# Sheet1.net
KiCad netlist of a schematic drawn in Altium Designer
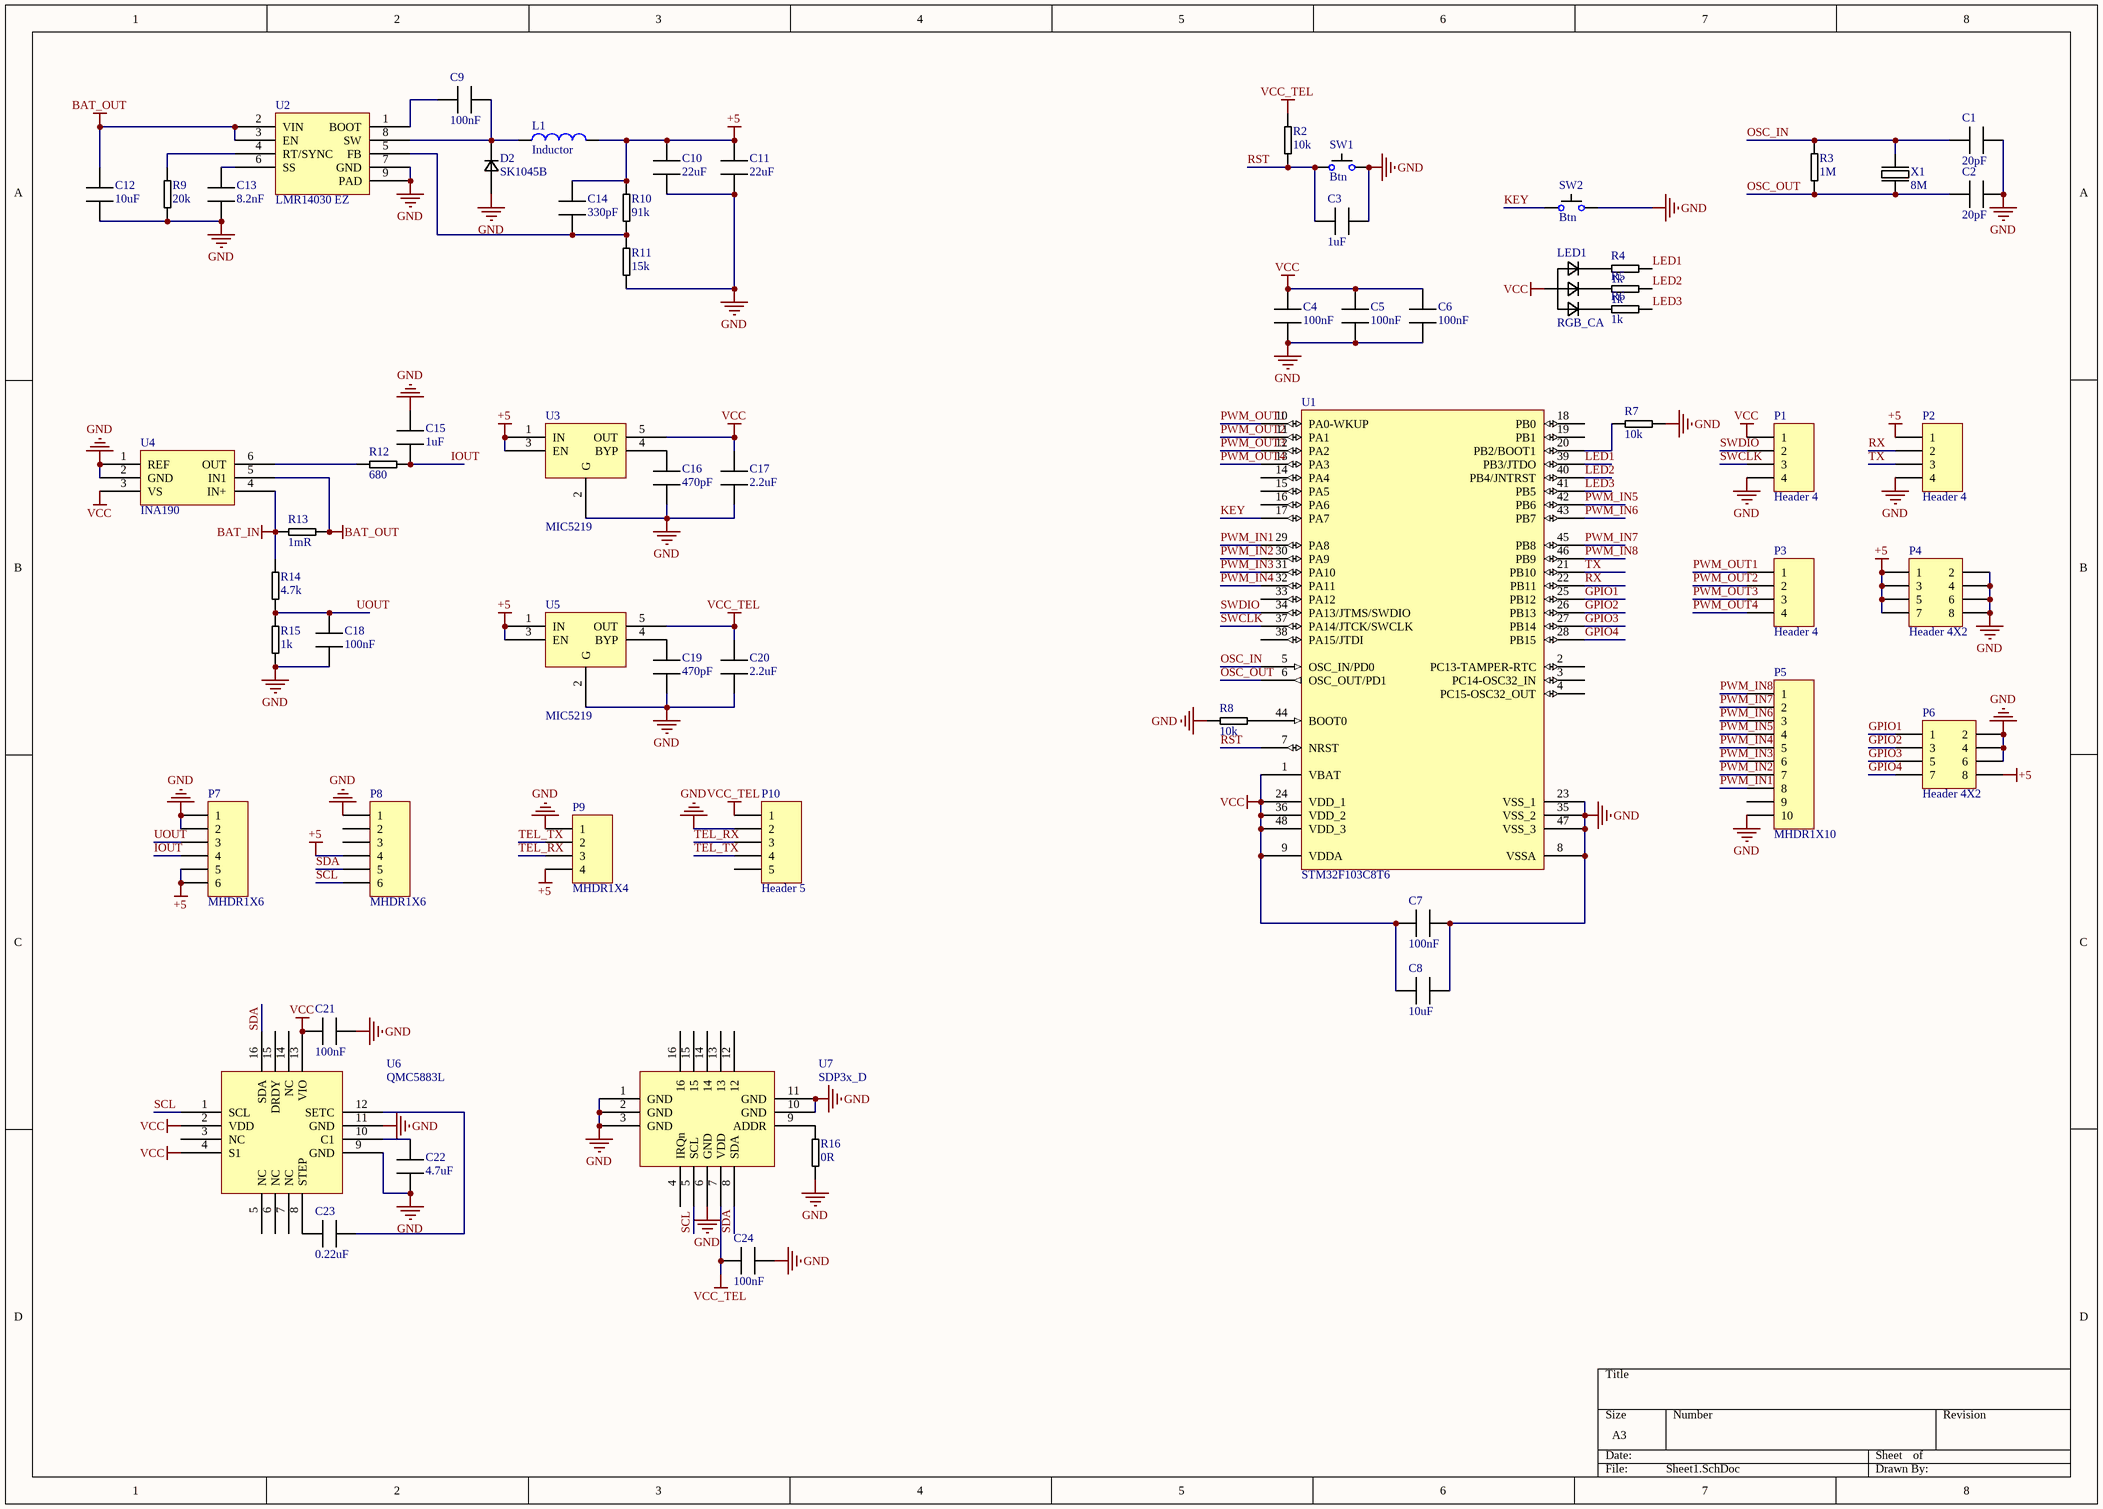
[diagram p0: Sheet1.SchDoc]

(export (version "E")
  (design (tool "Eeschema 10.0.6"))
  (components
    (comp (ref "C1") (value "20pF") (footprint "0603") (libsource (lib "LibCfrpg") (part "Cap")))
    (comp (ref "C2") (value "20pF") (footprint "0603") (libsource (lib "LibCfrpg") (part "Cap")))
    (comp (ref "C3") (value "1uF") (footprint "0603") (libsource (lib "LibCfrpg") (part "Cap")))
    (comp (ref "C4") (value "100nF") (footprint "0603") (libsource (lib "LibCfrpg") (part "Cap")))
    (comp (ref "C5") (value "100nF") (footprint "0603") (libsource (lib "LibCfrpg") (part "Cap")))
    (comp (ref "C6") (value "100nF") (footprint "0603") (libsource (lib "LibCfrpg") (part "Cap")))
    (comp (ref "C7") (value "100nF") (footprint "0603") (libsource (lib "LibCfrpg") (part "Cap")))
    (comp (ref "C8") (value "10uF") (footprint "0603") (libsource (lib "LibCfrpg") (part "Cap")))
    (comp (ref "C9") (value "100nF") (footprint "0603") (libsource (lib "LibCfrpg") (part "Cap")))
    (comp (ref "C10") (value "22uF") (footprint "0603") (libsource (lib "LibCfrpg") (part "Cap")))
    (comp (ref "C11") (value "22uF") (footprint "0603") (libsource (lib "LibCfrpg") (part "Cap")))
    (comp (ref "C12") (value "10uF") (footprint "1210") (libsource (lib "LibCfrpg") (part "Cap")))
    (comp (ref "C13") (value "8.2nF") (footprint "0603") (libsource (lib "LibCfrpg") (part "Cap")))
    (comp (ref "C14") (value "330pF") (footprint "0603") (libsource (lib "LibCfrpg") (part "Cap")))
    (comp (ref "C15") (value "1uF") (footprint "0603") (libsource (lib "LibCfrpg") (part "Cap")))
    (comp (ref "C16") (value "470pF") (footprint "0603") (libsource (lib "LibCfrpg") (part "Cap")))
    (comp (ref "C17") (value "2.2uF") (footprint "0603") (libsource (lib "LibCfrpg") (part "Cap")))
    (comp (ref "C18") (value "100nF") (footprint "0603") (libsource (lib "LibCfrpg") (part "Cap")))
    (comp (ref "C19") (value "470pF") (footprint "0603") (libsource (lib "LibCfrpg") (part "Cap")))
    (comp (ref "C20") (value "2.2uF") (footprint "0603") (libsource (lib "LibCfrpg") (part "Cap")))
    (comp (ref "C21") (value "100nF") (footprint "0603") (libsource (lib "LibCfrpg") (part "Cap")))
    (comp (ref "C22") (value "4.7uF") (footprint "0603") (libsource (lib "LibCfrpg") (part "Cap")))
    (comp (ref "C23") (value "0.22uF") (footprint "0603") (libsource (lib "LibCfrpg") (part "Cap")))
    (comp (ref "C24") (value "100nF") (footprint "0603") (libsource (lib "LibCfrpg") (part "Cap")))
    (comp (ref "D2")
      (value "SK1045B")
      (footprint "SMB (DO-214AA)")
      (libsource (lib "LibCfrpg") (part "Diode"))
    )
    (comp (ref "L1") (value "Inductor") (footprint "Ind1040") (libsource (lib "LibCfrpg") (part "Inductor")))
    (comp (ref "LED1") (value "RGB_CA") (footprint "RGB1.6*1.6") (libsource (lib "LibCfrpg") (part "RGB_CA")))
    (comp (ref "P1")
      (value "Header 4")
      (footprint "HDR1X4")
      (description "Header, 4-Pin")
      (fields (field (name "PUBLISHER") "Altium Limited"))
      (libsource (lib "Miscellaneous Connectors") (part "Header 4"))
    )
    (comp (ref "P2")
      (value "Header 4")
      (footprint "HDR1X4")
      (description "Header, 4-Pin")
      (fields (field (name "PUBLISHER") "Altium Limited"))
      (libsource (lib "Miscellaneous Connectors") (part "Header 4"))
    )
    (comp (ref "P3")
      (value "Header 4")
      (footprint "HDR1X4")
      (description "Header, 4-Pin")
      (fields (field (name "PUBLISHER") "Altium Limited"))
      (libsource (lib "Miscellaneous Connectors") (part "Header 4"))
    )
    (comp (ref "P4")
      (value "Header 4X2")
      (footprint "HDR2X4")
      (description "Header, 4-Pin, Dual row")
      (fields (field (name "PUBLISHER") "Altium Limited"))
      (libsource (lib "Miscellaneous Connectors") (part "Header 4X2"))
    )
    (comp (ref "P5")
      (value "MHDR1X10")
      (footprint "MHDR1X10")
      (description "Header, 10-Pin")
      (fields (field (name "PUBLISHER") "Altium Limited"))
      (libsource (lib "Miscellaneous Connectors") (part "MHDR1X10"))
    )
    (comp (ref "P6")
      (value "Header 4X2")
      (footprint "HDR2X4")
      (description "Header, 4-Pin, Dual row")
      (fields (field (name "PUBLISHER") "Altium Limited"))
      (libsource (lib "Miscellaneous Connectors") (part "Header 4X2"))
    )
    (comp (ref "P7")
      (value "MHDR1X6")
      (footprint "MHDR1X6")
      (description "Header, 6-Pin")
      (fields (field (name "PUBLISHER") "Altium Limited"))
      (libsource (lib "Miscellaneous Connectors") (part "MHDR1X6"))
    )
    (comp (ref "P8")
      (value "MHDR1X6")
      (footprint "MHDR1X6")
      (description "Header, 6-Pin")
      (fields (field (name "PUBLISHER") "Altium Limited"))
      (libsource (lib "Miscellaneous Connectors") (part "MHDR1X6"))
    )
    (comp (ref "P9")
      (value "MHDR1X4")
      (footprint "MHDR1X4")
      (description "Header, 4-Pin")
      (fields (field (name "PUBLISHER") "Altium Limited"))
      (libsource (lib "Miscellaneous Connectors") (part "MHDR1X4"))
    )
    (comp (ref "P10")
      (value "Header 5")
      (footprint "HDR1X5")
      (description "Header, 5-Pin")
      (fields (field (name "PUBLISHER") "Altium Limited"))
      (libsource (lib "Miscellaneous Connectors") (part "Header 5"))
    )
    (comp (ref "R2") (value "10k") (footprint "0603") (libsource (lib "LibCfrpg") (part "Res")))
    (comp (ref "R3") (value "1M") (footprint "0603") (libsource (lib "LibCfrpg") (part "Res")))
    (comp (ref "R4") (value "1k") (footprint "0603") (libsource (lib "LibCfrpg") (part "Res")))
    (comp (ref "R5") (value "1k") (footprint "0603") (libsource (lib "LibCfrpg") (part "Res")))
    (comp (ref "R6") (value "1k") (footprint "0603") (libsource (lib "LibCfrpg") (part "Res")))
    (comp (ref "R7") (value "10k") (footprint "0603") (libsource (lib "LibCfrpg") (part "Res")))
    (comp (ref "R8") (value "10k") (footprint "0603") (libsource (lib "LibCfrpg") (part "Res")))
    (comp (ref "R9") (value "20k") (footprint "0603") (libsource (lib "LibCfrpg") (part "Res")))
    (comp (ref "R10") (value "91k") (footprint "0603") (libsource (lib "LibCfrpg") (part "Res")))
    (comp (ref "R11") (value "15k") (footprint "0603") (libsource (lib "LibCfrpg") (part "Res")))
    (comp (ref "R12") (value "680") (footprint "0603") (libsource (lib "LibCfrpg") (part "Res")))
    (comp (ref "R13") (value "1mR") (footprint "2512") (libsource (lib "LibCfrpg") (part "Res")))
    (comp (ref "R14") (value "4.7k") (footprint "0603") (libsource (lib "LibCfrpg") (part "Res")))
    (comp (ref "R15") (value "1k") (footprint "0603") (libsource (lib "LibCfrpg") (part "Res")))
    (comp (ref "R16") (value "0R") (footprint "0603") (libsource (lib "LibCfrpg") (part "Res")))
    (comp (ref "SW1") (value "Btn") (footprint "BTN_B3U_B") (libsource (lib "LibCfrpg") (part "Btn")))
    (comp (ref "SW2") (value "Btn") (footprint "BTN_B3U_B") (libsource (lib "LibCfrpg") (part "Btn")))
    (comp (ref "U1")
      (value "STM32F103C8T6")
      (footprint "LQFP48_N")
      (description "STM32 ARM-based 32-bit MCU with 64 Kbytes Flash, 48-pin LQFP, Industrial Temperature")
      (fields (field (name "PUBLISHER") "Altium Limited"))
      (libsource (lib "ST Microcontroller 32-Bit STM32") (part "STM32F103C8T6"))
    )
    (comp (ref "U2")
      (value "LMR14030 EZ")
      (footprint "SOP8-Pad")
      (libsource (lib "LibCfrpg") (part "LMR14030 EZ"))
    )
    (comp (ref "U3") (value "MIC5219") (footprint "SOT23-5") (libsource (lib "LibCfrpg") (part "MIC5219")))
    (comp (ref "U4") (value "INA190") (footprint "SC70") (libsource (lib "LibCfrpg") (part "INA190")))
    (comp (ref "U5") (value "MIC5219") (footprint "SOT23-5") (libsource (lib "LibCfrpg") (part "MIC5219")))
    (comp (ref "U6") (value "QMC5883L") (footprint "QMC5883") (libsource (lib "LibCfrpg") (part "QMC5883L")))
    (comp (ref "U7") (value "SDP3x_D") (footprint "SDP3x") (libsource (lib "LibCfrpg") (part "SDP3x_D")))
    (comp (ref "X1") (value "8M") (footprint "XTAL-3225-4") (libsource (lib "LibCfrpg") (part "XTAL")))
  )
  (nets
    (net (code "1") (name "+5") (class "Default")
      (node (ref "C10") (pin "2") (pintype "passive"))
      (node (ref "C11") (pin "2") (pintype "passive"))
      (node (ref "C14") (pin "2") (pintype "passive"))
      (node (ref "L1") (pin "2") (pinfunction "2_2") (pintype "passive"))
      (node (ref "P2") (pin "1") (pinfunction "1_1") (pintype "passive"))
      (node (ref "P4") (pin "1") (pinfunction "1_1") (pintype "passive"))
      (node (ref "P4") (pin "3") (pinfunction "3_3") (pintype "passive"))
      (node (ref "P4") (pin "5") (pinfunction "5_5") (pintype "passive"))
      (node (ref "P4") (pin "7") (pinfunction "7_7") (pintype "passive"))
      (node (ref "P6") (pin "8") (pinfunction "8_8") (pintype "passive"))
      (node (ref "P7") (pin "5") (pinfunction "5_5") (pintype "passive"))
      (node (ref "P7") (pin "6") (pinfunction "6_6") (pintype "passive"))
      (node (ref "P8") (pin "4") (pinfunction "4_4") (pintype "passive"))
      (node (ref "P9") (pin "4") (pinfunction "4_4") (pintype "passive"))
      (node (ref "R10") (pin "2") (pintype "passive"))
      (node (ref "U3") (pin "1") (pinfunction "IN_1") (pintype "passive"))
      (node (ref "U3") (pin "3") (pinfunction "EN_3") (pintype "passive"))
      (node (ref "U5") (pin "1") (pinfunction "IN_1") (pintype "passive"))
      (node (ref "U5") (pin "3") (pinfunction "EN_3") (pintype "passive"))
    )
    (net (code "2") (name "/GPIO1") (class "Default")
      (node (ref "P6") (pin "1") (pinfunction "1_1") (pintype "passive"))
      (node (ref "U1") (pin "25") (pinfunction "PB12_25") (pintype "bidirectional"))
    )
    (net (code "3") (name "/GPIO2") (class "Default")
      (node (ref "P6") (pin "3") (pinfunction "3_3") (pintype "passive"))
      (node (ref "U1") (pin "26") (pinfunction "PB13_26") (pintype "bidirectional"))
    )
    (net (code "4") (name "/GPIO3") (class "Default")
      (node (ref "P6") (pin "5") (pinfunction "5_5") (pintype "passive"))
      (node (ref "U1") (pin "27") (pinfunction "PB14_27") (pintype "bidirectional"))
    )
    (net (code "5") (name "/GPIO4") (class "Default")
      (node (ref "P6") (pin "7") (pinfunction "7_7") (pintype "passive"))
      (node (ref "U1") (pin "28") (pinfunction "PB15_28") (pintype "bidirectional"))
    )
    (net (code "6") (name "/IOUT") (class "Default")
      (node (ref "C15") (pin "1") (pintype "passive"))
      (node (ref "P7") (pin "4") (pinfunction "4_4") (pintype "passive"))
      (node (ref "R12") (pin "2") (pintype "passive"))
    )
    (net (code "7") (name "/KEY") (class "Default")
      (node (ref "SW2") (pin "1") (pintype "passive"))
      (node (ref "U1") (pin "17") (pinfunction "PA7_17") (pintype "bidirectional"))
    )
    (net (code "8") (name "/LED1") (class "Default")
      (node (ref "R4") (pin "2") (pintype "passive"))
      (node (ref "U1") (pin "39") (pinfunction "PB3/JTDO_39") (pintype "bidirectional"))
    )
    (net (code "9") (name "/LED2") (class "Default")
      (node (ref "R5") (pin "2") (pintype "passive"))
      (node (ref "U1") (pin "40") (pinfunction "PB4/JNTRST_40") (pintype "bidirectional"))
    )
    (net (code "10") (name "/LED3") (class "Default")
      (node (ref "R6") (pin "2") (pintype "passive"))
      (node (ref "U1") (pin "41") (pinfunction "PB5_41") (pintype "bidirectional"))
    )
    (net (code "11") (name "/OSC_IN") (class "Default")
      (node (ref "C1") (pin "1") (pintype "passive"))
      (node (ref "R3") (pin "2") (pintype "passive"))
      (node (ref "U1") (pin "5") (pinfunction "OSC_IN/PD0_5") (pintype "input"))
      (node (ref "X1") (pin "2") (pintype "passive"))
    )
    (net (code "12") (name "/OSC_OUT") (class "Default")
      (node (ref "C2") (pin "1") (pintype "passive"))
      (node (ref "R3") (pin "1") (pintype "passive"))
      (node (ref "U1") (pin "6") (pinfunction "OSC_OUT/PD1_6") (pintype "output"))
      (node (ref "X1") (pin "1") (pintype "passive"))
    )
    (net (code "13") (name "/PWM_IN1") (class "Default")
      (node (ref "P5") (pin "8") (pinfunction "8_8") (pintype "passive"))
      (node (ref "U1") (pin "29") (pinfunction "PA8_29") (pintype "bidirectional"))
    )
    (net (code "14") (name "/PWM_IN2") (class "Default")
      (node (ref "P5") (pin "7") (pinfunction "7_7") (pintype "passive"))
      (node (ref "U1") (pin "30") (pinfunction "PA9_30") (pintype "bidirectional"))
    )
    (net (code "15") (name "/PWM_IN3") (class "Default")
      (node (ref "P5") (pin "6") (pinfunction "6_6") (pintype "passive"))
      (node (ref "U1") (pin "31") (pinfunction "PA10_31") (pintype "bidirectional"))
    )
    (net (code "16") (name "/PWM_IN4") (class "Default")
      (node (ref "P5") (pin "5") (pinfunction "5_5") (pintype "passive"))
      (node (ref "U1") (pin "32") (pinfunction "PA11_32") (pintype "bidirectional"))
    )
    (net (code "17") (name "/PWM_IN5") (class "Default")
      (node (ref "P5") (pin "4") (pinfunction "4_4") (pintype "passive"))
      (node (ref "U1") (pin "42") (pinfunction "PB6_42") (pintype "bidirectional"))
    )
    (net (code "18") (name "/PWM_IN6") (class "Default")
      (node (ref "P5") (pin "3") (pinfunction "3_3") (pintype "passive"))
      (node (ref "U1") (pin "43") (pinfunction "PB7_43") (pintype "bidirectional"))
    )
    (net (code "19") (name "/PWM_IN7") (class "Default")
      (node (ref "P5") (pin "2") (pinfunction "2_2") (pintype "passive"))
      (node (ref "U1") (pin "45") (pinfunction "PB8_45") (pintype "bidirectional"))
    )
    (net (code "20") (name "/PWM_IN8") (class "Default")
      (node (ref "P5") (pin "1") (pinfunction "1_1") (pintype "passive"))
      (node (ref "U1") (pin "46") (pinfunction "PB9_46") (pintype "bidirectional"))
    )
    (net (code "21") (name "/PWM_OUT1") (class "Default")
      (node (ref "P3") (pin "1") (pinfunction "1_1") (pintype "passive"))
      (node (ref "U1") (pin "10") (pinfunction "PA0-WKUP_10") (pintype "bidirectional"))
    )
    (net (code "22") (name "/PWM_OUT2") (class "Default")
      (node (ref "P3") (pin "2") (pinfunction "2_2") (pintype "passive"))
      (node (ref "U1") (pin "11") (pinfunction "PA1_11") (pintype "bidirectional"))
    )
    (net (code "23") (name "/PWM_OUT3") (class "Default")
      (node (ref "P3") (pin "3") (pinfunction "3_3") (pintype "passive"))
      (node (ref "U1") (pin "12") (pinfunction "PA2_12") (pintype "bidirectional"))
    )
    (net (code "24") (name "/PWM_OUT4") (class "Default")
      (node (ref "P3") (pin "4") (pinfunction "4_4") (pintype "passive"))
      (node (ref "U1") (pin "13") (pinfunction "PA3_13") (pintype "bidirectional"))
    )
    (net (code "25") (name "/RST") (class "Default")
      (node (ref "C3") (pin "1") (pintype "passive"))
      (node (ref "R2") (pin "1") (pintype "passive"))
      (node (ref "SW1") (pin "1") (pintype "passive"))
      (node (ref "U1") (pin "7") (pinfunction "NRST_7") (pintype "bidirectional"))
    )
    (net (code "26") (name "/RX") (class "Default")
      (node (ref "P2") (pin "2") (pinfunction "2_2") (pintype "passive"))
      (node (ref "U1") (pin "22") (pinfunction "PB11_22") (pintype "bidirectional"))
    )
    (net (code "27") (name "/SCL") (class "Default")
      (node (ref "P8") (pin "6") (pinfunction "6_6") (pintype "passive"))
      (node (ref "U6") (pin "1") (pinfunction "SCL_1") (pintype "passive"))
      (node (ref "U7") (pin "5") (pinfunction "SCL_5") (pintype "passive"))
    )
    (net (code "28") (name "/SDA") (class "Default")
      (node (ref "P8") (pin "5") (pinfunction "5_5") (pintype "passive"))
      (node (ref "U6") (pin "16") (pinfunction "SDA_16") (pintype "passive"))
      (node (ref "U7") (pin "8") (pinfunction "SDA_8") (pintype "passive"))
    )
    (net (code "29") (name "/SWCLK") (class "Default")
      (node (ref "P1") (pin "3") (pinfunction "3_3") (pintype "passive"))
      (node (ref "U1") (pin "37") (pinfunction "PA14/JTCK/SWCLK_37") (pintype "bidirectional"))
    )
    (net (code "30") (name "/SWDIO") (class "Default")
      (node (ref "P1") (pin "2") (pinfunction "2_2") (pintype "passive"))
      (node (ref "U1") (pin "34") (pinfunction "PA13/JTMS/SWDIO_34") (pintype "bidirectional"))
    )
    (net (code "31") (name "/TEL_RX") (class "Default")
      (node (ref "P10") (pin "3") (pinfunction "3_3") (pintype "passive"))
      (node (ref "P9") (pin "3") (pinfunction "3_3") (pintype "passive"))
    )
    (net (code "32") (name "/TEL_TX") (class "Default")
      (node (ref "P10") (pin "4") (pinfunction "4_4") (pintype "passive"))
      (node (ref "P9") (pin "2") (pinfunction "2_2") (pintype "passive"))
    )
    (net (code "33") (name "/TX") (class "Default")
      (node (ref "P2") (pin "3") (pinfunction "3_3") (pintype "passive"))
      (node (ref "U1") (pin "21") (pinfunction "PB10_21") (pintype "bidirectional"))
    )
    (net (code "34") (name "/UOUT") (class "Default")
      (node (ref "C18") (pin "2") (pintype "passive"))
      (node (ref "P7") (pin "3") (pinfunction "3_3") (pintype "passive"))
      (node (ref "R14") (pin "1") (pintype "passive"))
      (node (ref "R15") (pin "2") (pintype "passive"))
    )
    (net (code "35") (name "BAT_IN") (class "Default")
      (node (ref "R13") (pin "1") (pintype "passive"))
      (node (ref "R14") (pin "2") (pintype "passive"))
      (node (ref "U4") (pin "4") (pinfunction "IN+_4") (pintype "passive"))
    )
    (net (code "36") (name "BAT_OUT") (class "Default")
      (node (ref "C12") (pin "2") (pintype "passive"))
      (node (ref "R13") (pin "2") (pintype "passive"))
      (node (ref "U2") (pin "2") (pinfunction "VIN_2") (pintype "passive"))
      (node (ref "U2") (pin "3") (pinfunction "EN_3") (pintype "passive"))
      (node (ref "U4") (pin "5") (pinfunction "IN1_5") (pintype "passive"))
    )
    (net (code "37") (name "GND") (class "Default")
      (node (ref "C1") (pin "2") (pintype "passive"))
      (node (ref "C10") (pin "1") (pintype "passive"))
      (node (ref "C11") (pin "1") (pintype "passive"))
      (node (ref "C12") (pin "1") (pintype "passive"))
      (node (ref "C13") (pin "1") (pintype "passive"))
      (node (ref "C15") (pin "2") (pintype "passive"))
      (node (ref "C16") (pin "1") (pintype "passive"))
      (node (ref "C17") (pin "1") (pintype "passive"))
      (node (ref "C18") (pin "1") (pintype "passive"))
      (node (ref "C19") (pin "1") (pintype "passive"))
      (node (ref "C2") (pin "2") (pintype "passive"))
      (node (ref "C20") (pin "1") (pintype "passive"))
      (node (ref "C21") (pin "2") (pintype "passive"))
      (node (ref "C22") (pin "1") (pintype "passive"))
      (node (ref "C24") (pin "2") (pintype "passive"))
      (node (ref "C3") (pin "2") (pintype "passive"))
      (node (ref "C4") (pin "1") (pintype "passive"))
      (node (ref "C5") (pin "1") (pintype "passive"))
      (node (ref "C6") (pin "1") (pintype "passive"))
      (node (ref "C7") (pin "2") (pintype "passive"))
      (node (ref "C8") (pin "2") (pintype "passive"))
      (node (ref "D2") (pin "1") (pintype "passive"))
      (node (ref "P1") (pin "4") (pinfunction "4_4") (pintype "passive"))
      (node (ref "P10") (pin "2") (pinfunction "2_2") (pintype "passive"))
      (node (ref "P2") (pin "4") (pinfunction "4_4") (pintype "passive"))
      (node (ref "P4") (pin "2") (pinfunction "2_2") (pintype "passive"))
      (node (ref "P4") (pin "4") (pinfunction "4_4") (pintype "passive"))
      (node (ref "P4") (pin "6") (pinfunction "6_6") (pintype "passive"))
      (node (ref "P4") (pin "8") (pinfunction "8_8") (pintype "passive"))
      (node (ref "P5") (pin "10") (pinfunction "10_10") (pintype "passive"))
      (node (ref "P6") (pin "2") (pinfunction "2_2") (pintype "passive"))
      (node (ref "P6") (pin "4") (pinfunction "4_4") (pintype "passive"))
      (node (ref "P6") (pin "6") (pinfunction "6_6") (pintype "passive"))
      (node (ref "P7") (pin "1") (pinfunction "1_1") (pintype "passive"))
      (node (ref "P7") (pin "2") (pinfunction "2_2") (pintype "passive"))
      (node (ref "P8") (pin "1") (pinfunction "1_1") (pintype "passive"))
      (node (ref "P9") (pin "1") (pinfunction "1_1") (pintype "passive"))
      (node (ref "R11") (pin "1") (pintype "passive"))
      (node (ref "R15") (pin "1") (pintype "passive"))
      (node (ref "R16") (pin "1") (pintype "passive"))
      (node (ref "R7") (pin "2") (pintype "passive"))
      (node (ref "R8") (pin "1") (pintype "passive"))
      (node (ref "R9") (pin "1") (pintype "passive"))
      (node (ref "SW1") (pin "2") (pintype "passive"))
      (node (ref "SW2") (pin "2") (pintype "passive"))
      (node (ref "U1") (pin "23") (pinfunction "VSS_1_23") (pintype "power_in"))
      (node (ref "U1") (pin "35") (pinfunction "VSS_2_35") (pintype "power_in"))
      (node (ref "U1") (pin "47") (pinfunction "VSS_3_47") (pintype "power_in"))
      (node (ref "U1") (pin "8") (pinfunction "VSSA_8") (pintype "power_in"))
      (node (ref "U2") (pin "7") (pinfunction "GND_7") (pintype "passive"))
      (node (ref "U2") (pin "9") (pinfunction "PAD_9") (pintype "passive"))
      (node (ref "U3") (pin "2") (pinfunction "G_2") (pintype "passive"))
      (node (ref "U4") (pin "1") (pinfunction "REF_1") (pintype "passive"))
      (node (ref "U4") (pin "2") (pinfunction "GND_2") (pintype "passive"))
      (node (ref "U5") (pin "2") (pinfunction "G_2") (pintype "passive"))
      (node (ref "U6") (pin "11") (pinfunction "GND_11") (pintype "passive"))
      (node (ref "U6") (pin "9") (pinfunction "GND_9") (pintype "passive"))
      (node (ref "U7") (pin "1") (pinfunction "GND_1") (pintype "passive"))
      (node (ref "U7") (pin "10") (pinfunction "GND_10") (pintype "passive"))
      (node (ref "U7") (pin "11") (pinfunction "GND_11") (pintype "passive"))
      (node (ref "U7") (pin "2") (pinfunction "GND_2") (pintype "passive"))
      (node (ref "U7") (pin "3") (pinfunction "GND_3") (pintype "passive"))
      (node (ref "U7") (pin "6") (pinfunction "GND_6") (pintype "passive"))
    )
    (net (code "38") (name "Net-(LED1-Pad1)") (class "Default")
      (node (ref "LED1") (pin "1") (pintype "passive"))
      (node (ref "R4") (pin "1") (pintype "passive"))
    )
    (net (code "39") (name "Net-(LED1-Pad2)") (class "Default")
      (node (ref "LED1") (pin "2") (pintype "passive"))
      (node (ref "R5") (pin "1") (pintype "passive"))
    )
    (net (code "40") (name "Net-(LED1-Pad3)") (class "Default")
      (node (ref "LED1") (pin "3") (pintype "passive"))
      (node (ref "R6") (pin "1") (pintype "passive"))
    )
    (net (code "41") (name "Net-(U1-BOOT0)") (class "Default")
      (node (ref "R8") (pin "2") (pintype "passive"))
      (node (ref "U1") (pin "44") (pinfunction "BOOT0_44") (pintype "input"))
    )
    (net (code "42") (name "Net-(U1-PB2{slash}BOOT1)") (class "Default")
      (node (ref "R7") (pin "1") (pintype "passive"))
      (node (ref "U1") (pin "20") (pinfunction "PB2/BOOT1_20") (pintype "bidirectional"))
    )
    (net (code "43") (name "Net-(U2-BOOT)") (class "Default")
      (node (ref "C9") (pin "1") (pintype "passive"))
      (node (ref "U2") (pin "1") (pinfunction "BOOT_1") (pintype "passive"))
    )
    (net (code "44") (name "Net-(U2-FB)") (class "Default")
      (node (ref "C14") (pin "1") (pintype "passive"))
      (node (ref "R10") (pin "1") (pintype "passive"))
      (node (ref "R11") (pin "2") (pintype "passive"))
      (node (ref "U2") (pin "5") (pinfunction "FB_5") (pintype "passive"))
    )
    (net (code "45") (name "Net-(U2-RT{slash}SYNC)") (class "Default")
      (node (ref "R9") (pin "2") (pintype "passive"))
      (node (ref "U2") (pin "4") (pinfunction "RT/SYNC_4") (pintype "passive"))
    )
    (net (code "46") (name "Net-(U2-SS)") (class "Default")
      (node (ref "C13") (pin "2") (pintype "passive"))
      (node (ref "U2") (pin "6") (pinfunction "SS_6") (pintype "passive"))
    )
    (net (code "47") (name "Net-(U2-SW)") (class "Default")
      (node (ref "C9") (pin "2") (pintype "passive"))
      (node (ref "D2") (pin "2") (pintype "passive"))
      (node (ref "L1") (pin "1") (pinfunction "1_1") (pintype "passive"))
      (node (ref "U2") (pin "8") (pinfunction "SW_8") (pintype "passive"))
    )
    (net (code "48") (name "Net-(U3-BYP)") (class "Default")
      (node (ref "C16") (pin "2") (pintype "passive"))
      (node (ref "U3") (pin "4") (pinfunction "BYP_4") (pintype "passive"))
    )
    (net (code "49") (name "Net-(U4-OUT)") (class "Default")
      (node (ref "R12") (pin "1") (pintype "passive"))
      (node (ref "U4") (pin "6") (pinfunction "OUT_6") (pintype "passive"))
    )
    (net (code "50") (name "Net-(U5-BYP)") (class "Default")
      (node (ref "C19") (pin "2") (pintype "passive"))
      (node (ref "U5") (pin "4") (pinfunction "BYP_4") (pintype "passive"))
    )
    (net (code "51") (name "Net-(U6-C1)") (class "Default")
      (node (ref "C22") (pin "2") (pintype "passive"))
      (node (ref "U6") (pin "10") (pinfunction "C1_10") (pintype "passive"))
    )
    (net (code "52") (name "Net-(U6-SETC)") (class "Default")
      (node (ref "C23") (pin "2") (pintype "passive"))
      (node (ref "U6") (pin "12") (pinfunction "SETC_12") (pintype "passive"))
    )
    (net (code "53") (name "Net-(U6-STEP)") (class "Default")
      (node (ref "C23") (pin "1") (pintype "passive"))
      (node (ref "U6") (pin "8") (pinfunction "STEP_8") (pintype "passive"))
    )
    (net (code "54") (name "Net-(U7-ADDR)") (class "Default")
      (node (ref "R16") (pin "2") (pintype "passive"))
      (node (ref "U7") (pin "9") (pinfunction "ADDR_9") (pintype "passive"))
    )
    (net (code "55") (name "VCC") (class "Default")
      (node (ref "C17") (pin "2") (pintype "passive"))
      (node (ref "C21") (pin "1") (pintype "passive"))
      (node (ref "C4") (pin "2") (pintype "passive"))
      (node (ref "C5") (pin "2") (pintype "passive"))
      (node (ref "C6") (pin "2") (pintype "passive"))
      (node (ref "C7") (pin "1") (pintype "passive"))
      (node (ref "C8") (pin "1") (pintype "passive"))
      (node (ref "LED1") (pin "4") (pintype "passive"))
      (node (ref "P1") (pin "1") (pinfunction "1_1") (pintype "passive"))
      (node (ref "U1") (pin "1") (pinfunction "VBAT_1") (pintype "power_in"))
      (node (ref "U1") (pin "24") (pinfunction "VDD_1_24") (pintype "power_in"))
      (node (ref "U1") (pin "36") (pinfunction "VDD_2_36") (pintype "power_in"))
      (node (ref "U1") (pin "48") (pinfunction "VDD_3_48") (pintype "power_in"))
      (node (ref "U1") (pin "9") (pinfunction "VDDA_9") (pintype "power_in"))
      (node (ref "U3") (pin "5") (pinfunction "OUT_5") (pintype "passive"))
      (node (ref "U4") (pin "3") (pinfunction "VS_3") (pintype "passive"))
      (node (ref "U6") (pin "13") (pinfunction "VIO_13") (pintype "passive"))
      (node (ref "U6") (pin "2") (pinfunction "VDD_2") (pintype "passive"))
      (node (ref "U6") (pin "4") (pinfunction "S1_4") (pintype "passive"))
    )
    (net (code "56") (name "VCC_TEL") (class "Default")
      (node (ref "C20") (pin "2") (pintype "passive"))
      (node (ref "C24") (pin "1") (pintype "passive"))
      (node (ref "P10") (pin "1") (pinfunction "1_1") (pintype "passive"))
      (node (ref "R2") (pin "2") (pintype "passive"))
      (node (ref "U5") (pin "5") (pinfunction "OUT_5") (pintype "passive"))
      (node (ref "U7") (pin "7") (pinfunction "VDD_7") (pintype "passive"))
    )
    (net (code "57") (name "unconnected-(P5-Pad9)") (class "Default")
      (node (ref "P5") (pin "9") (pinfunction "9_9") (pintype "passive"))
    )
    (net (code "58") (name "unconnected-(P8-Pad2)") (class "Default")
      (node (ref "P8") (pin "2") (pinfunction "2_2") (pintype "passive"))
    )
    (net (code "59") (name "unconnected-(P8-Pad3)") (class "Default")
      (node (ref "P8") (pin "3") (pinfunction "3_3") (pintype "passive"))
    )
    (net (code "60") (name "unconnected-(P10-Pad5)") (class "Default")
      (node (ref "P10") (pin "5") (pinfunction "5_5") (pintype "passive"))
    )
    (net (code "61") (name "unconnected-(U1-PA4-Pad14)") (class "Default")
      (node (ref "U1") (pin "14") (pinfunction "PA4_14") (pintype "bidirectional"))
    )
    (net (code "62") (name "unconnected-(U1-PA5-Pad15)") (class "Default")
      (node (ref "U1") (pin "15") (pinfunction "PA5_15") (pintype "bidirectional"))
    )
    (net (code "63") (name "unconnected-(U1-PA6-Pad16)") (class "Default")
      (node (ref "U1") (pin "16") (pinfunction "PA6_16") (pintype "bidirectional"))
    )
    (net (code "64") (name "unconnected-(U1-PA12-Pad33)") (class "Default")
      (node (ref "U1") (pin "33") (pinfunction "PA12_33") (pintype "bidirectional"))
    )
    (net (code "65") (name "unconnected-(U1-PA15{slash}JTDI-Pad38)") (class "Default")
      (node (ref "U1") (pin "38") (pinfunction "PA15/JTDI_38") (pintype "bidirectional"))
    )
    (net (code "66") (name "unconnected-(U1-PB0-Pad18)") (class "Default")
      (node (ref "U1") (pin "18") (pinfunction "PB0_18") (pintype "bidirectional"))
    )
    (net (code "67") (name "unconnected-(U1-PB1-Pad19)") (class "Default")
      (node (ref "U1") (pin "19") (pinfunction "PB1_19") (pintype "bidirectional"))
    )
    (net (code "68") (name "unconnected-(U1-PC13-TAMPER-RTC-Pad2)") (class "Default")
      (node (ref "U1") (pin "2") (pinfunction "PC13-TAMPER-RTC_2") (pintype "bidirectional"))
    )
    (net (code "69") (name "unconnected-(U1-PC14-OSC32_IN-Pad3)") (class "Default")
      (node (ref "U1") (pin "3") (pinfunction "PC14-OSC32_IN_3") (pintype "bidirectional"))
    )
    (net (code "70") (name "unconnected-(U1-PC15-OSC32_OUT-Pad4)") (class "Default")
      (node (ref "U1") (pin "4") (pinfunction "PC15-OSC32_OUT_4") (pintype "bidirectional"))
    )
    (net (code "71") (name "unconnected-(U6-DRDY-Pad15)") (class "Default")
      (node (ref "U6") (pin "15") (pinfunction "DRDY_15") (pintype "passive"))
    )
    (net (code "72") (name "unconnected-(U6-NC-Pad3)") (class "Default")
      (node (ref "U6") (pin "3") (pinfunction "NC_3") (pintype "passive"))
    )
    (net (code "73") (name "unconnected-(U6-NC-Pad5)") (class "Default")
      (node (ref "U6") (pin "5") (pinfunction "NC_5") (pintype "passive"))
    )
    (net (code "74") (name "unconnected-(U6-NC-Pad6)") (class "Default")
      (node (ref "U6") (pin "6") (pinfunction "NC_6") (pintype "passive"))
    )
    (net (code "75") (name "unconnected-(U6-NC-Pad7)") (class "Default")
      (node (ref "U6") (pin "7") (pinfunction "NC_7") (pintype "passive"))
    )
    (net (code "76") (name "unconnected-(U6-NC-Pad14)") (class "Default")
      (node (ref "U6") (pin "14") (pinfunction "NC_14") (pintype "passive"))
    )
    (net (code "77") (name "unconnected-(U7-IRQn-Pad4)") (class "Default")
      (node (ref "U7") (pin "4") (pinfunction "IRQn_4") (pintype "passive"))
    )
    (net (code "78") (name "unconnected-(U7-Pad12)") (class "Default")
      (node (ref "U7") (pin "12") (pinfunction "12_12") (pintype "passive"))
    )
    (net (code "79") (name "unconnected-(U7-Pad13)") (class "Default")
      (node (ref "U7") (pin "13") (pinfunction "13_13") (pintype "passive"))
    )
    (net (code "80") (name "unconnected-(U7-Pad14)") (class "Default")
      (node (ref "U7") (pin "14") (pinfunction "14_14") (pintype "passive"))
    )
    (net (code "81") (name "unconnected-(U7-Pad15)") (class "Default")
      (node (ref "U7") (pin "15") (pinfunction "15_15") (pintype "passive"))
    )
    (net (code "82") (name "unconnected-(U7-Pad16)") (class "Default")
      (node (ref "U7") (pin "16") (pinfunction "16_16") (pintype "passive"))
    )
  )
)
